# Part07_NorFlash.net
KiCad netlist of a schematic drawn in Altium Designer
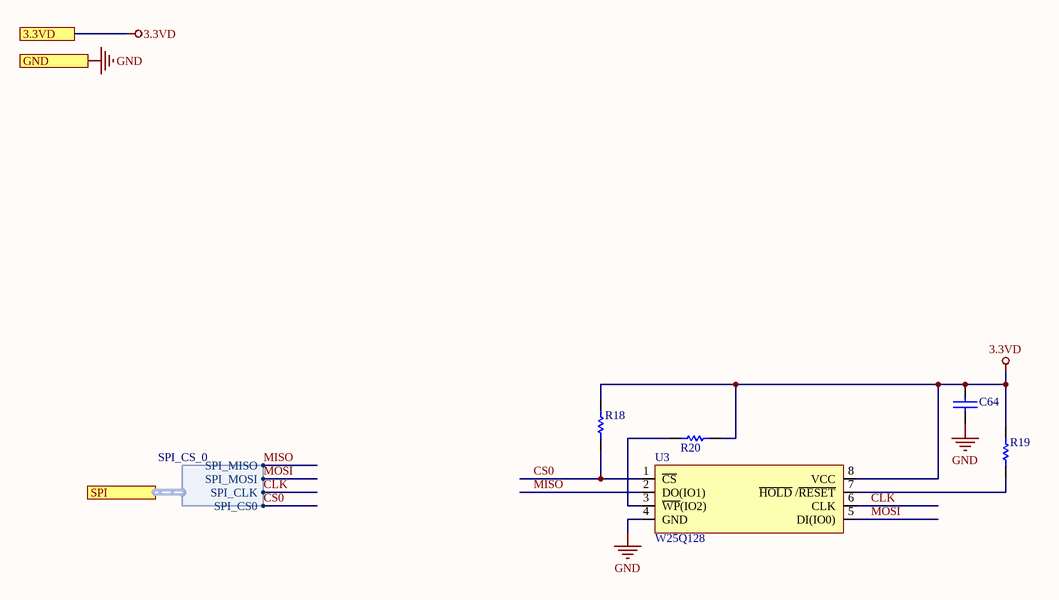
[diagram p0: Part07_NorFlash.SchDoc]

(export (version "E")
  (design (tool "Eeschema 10.0.6"))
  (components
    (comp (ref "C64")
      (value "0.1uF/16V")
      (footprint "0402C")
      (description "无极性电容")
      (libsource (lib "电容") (part "CAP"))
    )
    (comp (ref "R18") (value "RES") (footprint "0402R") (libsource (lib "电阻") (part "RES")))
    (comp (ref "R19") (value "RES") (footprint "0402R") (libsource (lib "电阻") (part "RES")))
    (comp (ref "R20") (value "RES") (footprint "0402R") (libsource (lib "电阻") (part "RES")))
    (comp (ref "U3") (value "W25Q128") (footprint "SOP8") (libsource (lib "MT7688_Lib") (part "W25Q128")))
  )
  (nets
    (net (code "2") (name "/CLK") (class "Default")
      (node (ref "U3") (pin "6") (pinfunction "CLK_6") (pintype "passive"))
    )
    (net (code "3") (name "/CS0") (class "Default")
      (node (ref "R18") (pin "2") (pinfunction "2_2") (pintype "passive"))
      (node (ref "U3") (pin "1") (pinfunction "~{CS}_1") (pintype "passive"))
    )
    (net (code "4") (name "/MISO") (class "Default")
      (node (ref "U3") (pin "2") (pinfunction "DO(IO1)_2") (pintype "passive"))
    )
    (net (code "5") (name "/MOSI") (class "Default")
      (node (ref "U3") (pin "5") (pinfunction "DI(IO0)_5") (pintype "passive"))
    )
    (net (code "7") (name "3.3VD") (class "Default")
      (node (ref "C64") (pin "1") (pinfunction "1_1") (pintype "passive"))
      (node (ref "R18") (pin "1") (pinfunction "1_1") (pintype "passive"))
      (node (ref "R19") (pin "1") (pinfunction "1_1") (pintype "passive"))
      (node (ref "R20") (pin "2") (pinfunction "2_2") (pintype "passive"))
      (node (ref "U3") (pin "8") (pinfunction "VCC_8") (pintype "passive"))
    )
    (net (code "8") (name "GND") (class "Default")
      (node (ref "C64") (pin "2") (pinfunction "2_2") (pintype "passive"))
      (node (ref "U3") (pin "4") (pinfunction "GND_4") (pintype "passive"))
    )
    (net (code "9") (name "Net-(U3-~{HOLD}_{slash}~{RESET})") (class "Default")
      (node (ref "R19") (pin "2") (pinfunction "2_2") (pintype "passive"))
      (node (ref "U3") (pin "7") (pinfunction "~{HOLD}_/~{RESET}_7") (pintype "passive"))
    )
    (net (code "10") (name "Net-(U3-~{WP}(IO2))") (class "Default")
      (node (ref "R20") (pin "1") (pinfunction "1_1") (pintype "passive"))
      (node (ref "U3") (pin "3") (pinfunction "~{WP}(IO2)_3") (pintype "passive"))
    )
  )
)
